# RAM_Board_trex.net
KiCad netlist of a schematic drawn in EAGLE
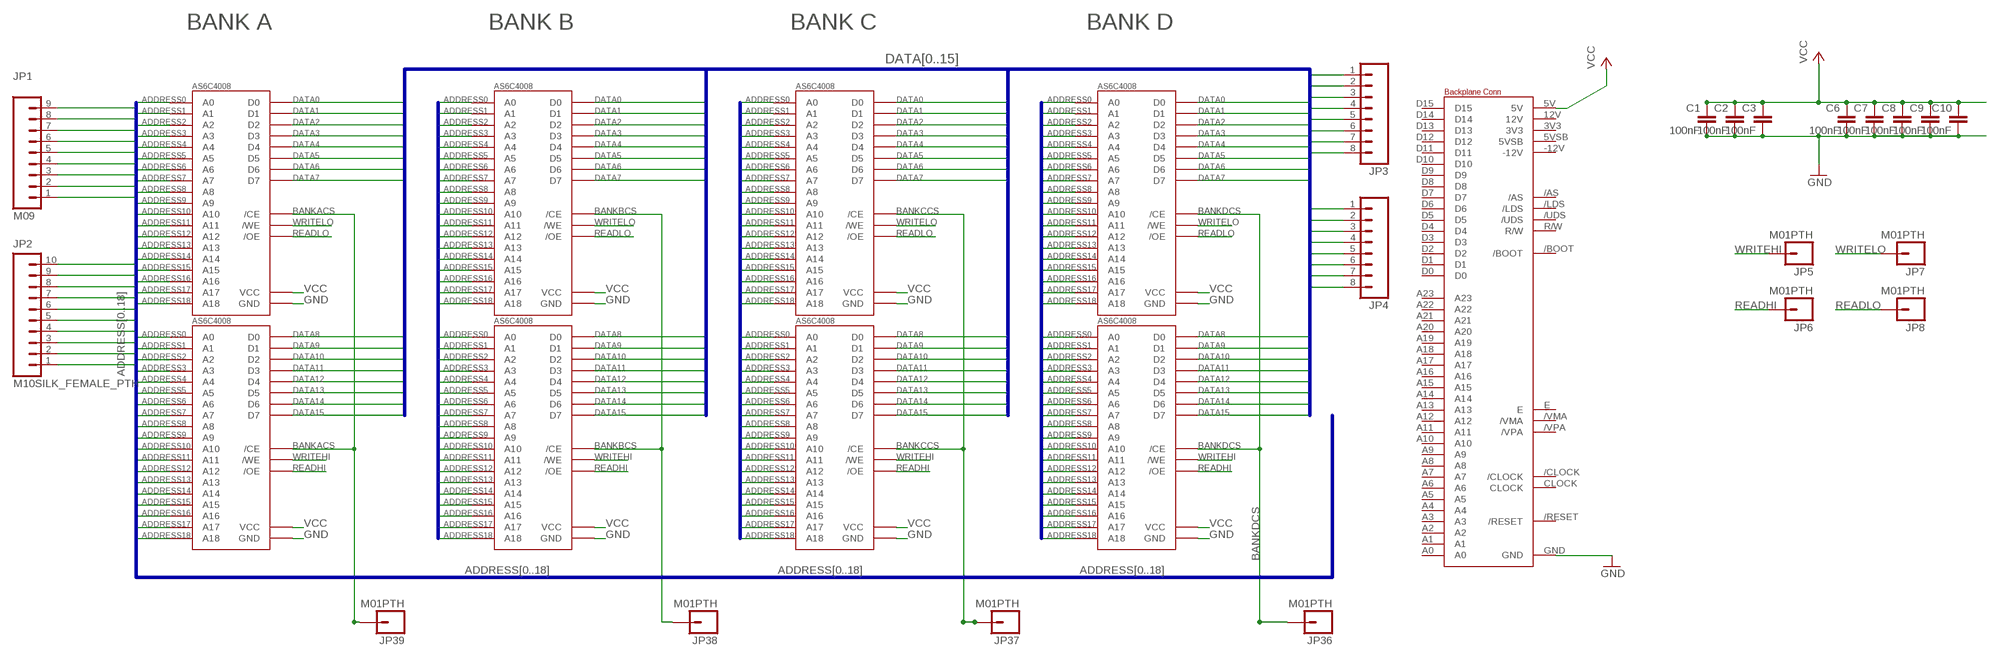
[diagram p0: schematic, sheet 1]

(export (version "E")
  (design (tool "Eeschema 10.0.6"))
  (components
    (comp (ref "AH")
      (value "AS6C4008")
      (footprint "eagle-import:DIL32")
      (libsource (lib "eagle-import") (part "AS6C4008"))
    )
    (comp (ref "AL")
      (value "AS6C4008")
      (footprint "eagle-import:DIL32")
      (libsource (lib "eagle-import") (part "AS6C4008"))
    )
    (comp (ref "BH")
      (value "AS6C4008")
      (footprint "eagle-import:DIL32")
      (libsource (lib "eagle-import") (part "AS6C4008"))
    )
    (comp (ref "BL")
      (value "AS6C4008")
      (footprint "eagle-import:DIL32")
      (libsource (lib "eagle-import") (part "AS6C4008"))
    )
    (comp (ref "C1")
      (value "100nF")
      (footprint "eagle-import:CAP-PTH-SMALL")
      (libsource (lib "eagle-import") (part "CAPPTH"))
    )
    (comp (ref "C2")
      (value "100nF")
      (footprint "eagle-import:CAP-PTH-SMALL")
      (libsource (lib "eagle-import") (part "CAPPTH"))
    )
    (comp (ref "C3")
      (value "100nF")
      (footprint "eagle-import:CAP-PTH-SMALL")
      (libsource (lib "eagle-import") (part "CAPPTH"))
    )
    (comp (ref "C6")
      (value "100nF")
      (footprint "eagle-import:CAP-PTH-SMALL")
      (libsource (lib "eagle-import") (part "CAPPTH"))
    )
    (comp (ref "C7")
      (value "100nF")
      (footprint "eagle-import:CAP-PTH-SMALL")
      (libsource (lib "eagle-import") (part "CAPPTH"))
    )
    (comp (ref "C8")
      (value "100nF")
      (footprint "eagle-import:CAP-PTH-SMALL")
      (libsource (lib "eagle-import") (part "CAPPTH"))
    )
    (comp (ref "C9")
      (value "100nF")
      (footprint "eagle-import:CAP-PTH-SMALL")
      (libsource (lib "eagle-import") (part "CAPPTH"))
    )
    (comp (ref "C10")
      (value "100nF")
      (footprint "eagle-import:CAP-PTH-SMALL")
      (libsource (lib "eagle-import") (part "CAPPTH"))
    )
    (comp (ref "CH")
      (value "AS6C4008")
      (footprint "eagle-import:DIL32")
      (libsource (lib "eagle-import") (part "AS6C4008"))
    )
    (comp (ref "CL")
      (value "AS6C4008")
      (footprint "eagle-import:DIL32")
      (libsource (lib "eagle-import") (part "AS6C4008"))
    )
    (comp (ref "DH")
      (value "AS6C4008")
      (footprint "eagle-import:DIL32")
      (libsource (lib "eagle-import") (part "AS6C4008"))
    )
    (comp (ref "DL")
      (value "AS6C4008")
      (footprint "eagle-import:DIL32")
      (libsource (lib "eagle-import") (part "AS6C4008"))
    )
    (comp (ref "JP1")
      (value "M09")
      (footprint "eagle-import:1X09")
      (libsource (lib "eagle-import") (part "M09"))
    )
    (comp (ref "JP2")
      (value "M10SILK_FEMALE_PTH")
      (footprint "eagle-import:1X10")
      (libsource (lib "eagle-import") (part "M10SILK_FEMALE_PTH"))
    )
    (comp (ref "JP3")
      (value "M08")
      (footprint "eagle-import:1X08_ROUND")
      (libsource (lib "eagle-import") (part "M08"))
    )
    (comp (ref "JP4")
      (value "M08")
      (footprint "eagle-import:1X08_ROUND")
      (libsource (lib "eagle-import") (part "M08"))
    )
    (comp (ref "JP5")
      (value "M01PTH")
      (footprint "eagle-import:1X01")
      (libsource (lib "eagle-import") (part "M01PTH"))
    )
    (comp (ref "JP6")
      (value "M01PTH")
      (footprint "eagle-import:1X01")
      (libsource (lib "eagle-import") (part "M01PTH"))
    )
    (comp (ref "JP7")
      (value "M01PTH")
      (footprint "eagle-import:1X01")
      (libsource (lib "eagle-import") (part "M01PTH"))
    )
    (comp (ref "JP8")
      (value "M01PTH")
      (footprint "eagle-import:1X01")
      (libsource (lib "eagle-import") (part "M01PTH"))
    )
    (comp (ref "JP36")
      (value "M01PTH")
      (footprint "eagle-import:1X01")
      (libsource (lib "eagle-import") (part "M01PTH"))
    )
    (comp (ref "JP37")
      (value "M01PTH")
      (footprint "eagle-import:1X01")
      (libsource (lib "eagle-import") (part "M01PTH"))
    )
    (comp (ref "JP38")
      (value "M01PTH")
      (footprint "eagle-import:1X01")
      (libsource (lib "eagle-import") (part "M01PTH"))
    )
    (comp (ref "JP39")
      (value "M01PTH")
      (footprint "eagle-import:1X01")
      (libsource (lib "eagle-import") (part "M01PTH"))
    )
    (comp (ref "U$1")
      (value "BACKPLANECONN")
      (footprint "eagle-import:BLANKBOARD")
      (libsource (lib "eagle-import") (part "BACKPLANECONN"))
    )
  )
  (nets
    (net (code "3") (name "ADDRESS0") (class "Default")
      (node (ref "AH") (pin "12") (pinfunction "A0_12") (pintype "input"))
      (node (ref "AL") (pin "12") (pinfunction "A0_12") (pintype "input"))
      (node (ref "BH") (pin "12") (pinfunction "A0_12") (pintype "input"))
      (node (ref "BL") (pin "12") (pinfunction "A0_12") (pintype "input"))
      (node (ref "CH") (pin "12") (pinfunction "A0_12") (pintype "input"))
      (node (ref "CL") (pin "12") (pinfunction "A0_12") (pintype "input"))
      (node (ref "DH") (pin "12") (pinfunction "A0_12") (pintype "input"))
      (node (ref "DL") (pin "12") (pinfunction "A0_12") (pintype "input"))
      (node (ref "JP1") (pin "9") (pinfunction "9_9") (pintype "passive"))
    )
    (net (code "4") (name "ADDRESS1") (class "Default")
      (node (ref "AH") (pin "11") (pinfunction "A1_11") (pintype "input"))
      (node (ref "AL") (pin "11") (pinfunction "A1_11") (pintype "input"))
      (node (ref "BH") (pin "11") (pinfunction "A1_11") (pintype "input"))
      (node (ref "BL") (pin "11") (pinfunction "A1_11") (pintype "input"))
      (node (ref "CH") (pin "11") (pinfunction "A1_11") (pintype "input"))
      (node (ref "CL") (pin "11") (pinfunction "A1_11") (pintype "input"))
      (node (ref "DH") (pin "11") (pinfunction "A1_11") (pintype "input"))
      (node (ref "DL") (pin "11") (pinfunction "A1_11") (pintype "input"))
      (node (ref "JP1") (pin "8") (pinfunction "8_8") (pintype "passive"))
    )
    (net (code "5") (name "ADDRESS2") (class "Default")
      (node (ref "AH") (pin "10") (pinfunction "A2_10") (pintype "input"))
      (node (ref "AL") (pin "10") (pinfunction "A2_10") (pintype "input"))
      (node (ref "BH") (pin "10") (pinfunction "A2_10") (pintype "input"))
      (node (ref "BL") (pin "10") (pinfunction "A2_10") (pintype "input"))
      (node (ref "CH") (pin "10") (pinfunction "A2_10") (pintype "input"))
      (node (ref "CL") (pin "10") (pinfunction "A2_10") (pintype "input"))
      (node (ref "DH") (pin "10") (pinfunction "A2_10") (pintype "input"))
      (node (ref "DL") (pin "10") (pinfunction "A2_10") (pintype "input"))
      (node (ref "JP1") (pin "7") (pinfunction "7_7") (pintype "passive"))
    )
    (net (code "6") (name "ADDRESS3") (class "Default")
      (node (ref "AH") (pin "9") (pinfunction "A3_9") (pintype "input"))
      (node (ref "AL") (pin "9") (pinfunction "A3_9") (pintype "input"))
      (node (ref "BH") (pin "9") (pinfunction "A3_9") (pintype "input"))
      (node (ref "BL") (pin "9") (pinfunction "A3_9") (pintype "input"))
      (node (ref "CH") (pin "9") (pinfunction "A3_9") (pintype "input"))
      (node (ref "CL") (pin "9") (pinfunction "A3_9") (pintype "input"))
      (node (ref "DH") (pin "9") (pinfunction "A3_9") (pintype "input"))
      (node (ref "DL") (pin "9") (pinfunction "A3_9") (pintype "input"))
      (node (ref "JP1") (pin "6") (pinfunction "6_6") (pintype "passive"))
    )
    (net (code "7") (name "ADDRESS4") (class "Default")
      (node (ref "AH") (pin "8") (pinfunction "A4_8") (pintype "input"))
      (node (ref "AL") (pin "8") (pinfunction "A4_8") (pintype "input"))
      (node (ref "BH") (pin "8") (pinfunction "A4_8") (pintype "input"))
      (node (ref "BL") (pin "8") (pinfunction "A4_8") (pintype "input"))
      (node (ref "CH") (pin "8") (pinfunction "A4_8") (pintype "input"))
      (node (ref "CL") (pin "8") (pinfunction "A4_8") (pintype "input"))
      (node (ref "DH") (pin "8") (pinfunction "A4_8") (pintype "input"))
      (node (ref "DL") (pin "8") (pinfunction "A4_8") (pintype "input"))
      (node (ref "JP1") (pin "5") (pinfunction "5_5") (pintype "passive"))
    )
    (net (code "8") (name "ADDRESS5") (class "Default")
      (node (ref "AH") (pin "7") (pinfunction "A5_7") (pintype "input"))
      (node (ref "AL") (pin "7") (pinfunction "A5_7") (pintype "input"))
      (node (ref "BH") (pin "7") (pinfunction "A5_7") (pintype "input"))
      (node (ref "BL") (pin "7") (pinfunction "A5_7") (pintype "input"))
      (node (ref "CH") (pin "7") (pinfunction "A5_7") (pintype "input"))
      (node (ref "CL") (pin "7") (pinfunction "A5_7") (pintype "input"))
      (node (ref "DH") (pin "7") (pinfunction "A5_7") (pintype "input"))
      (node (ref "DL") (pin "7") (pinfunction "A5_7") (pintype "input"))
      (node (ref "JP1") (pin "4") (pinfunction "4_4") (pintype "passive"))
    )
    (net (code "9") (name "ADDRESS6") (class "Default")
      (node (ref "AH") (pin "6") (pinfunction "A6_6") (pintype "input"))
      (node (ref "AL") (pin "6") (pinfunction "A6_6") (pintype "input"))
      (node (ref "BH") (pin "6") (pinfunction "A6_6") (pintype "input"))
      (node (ref "BL") (pin "6") (pinfunction "A6_6") (pintype "input"))
      (node (ref "CH") (pin "6") (pinfunction "A6_6") (pintype "input"))
      (node (ref "CL") (pin "6") (pinfunction "A6_6") (pintype "input"))
      (node (ref "DH") (pin "6") (pinfunction "A6_6") (pintype "input"))
      (node (ref "DL") (pin "6") (pinfunction "A6_6") (pintype "input"))
      (node (ref "JP1") (pin "3") (pinfunction "3_3") (pintype "passive"))
    )
    (net (code "10") (name "ADDRESS7") (class "Default")
      (node (ref "AH") (pin "5") (pinfunction "A7_5") (pintype "input"))
      (node (ref "AL") (pin "5") (pinfunction "A7_5") (pintype "input"))
      (node (ref "BH") (pin "5") (pinfunction "A7_5") (pintype "input"))
      (node (ref "BL") (pin "5") (pinfunction "A7_5") (pintype "input"))
      (node (ref "CH") (pin "5") (pinfunction "A7_5") (pintype "input"))
      (node (ref "CL") (pin "5") (pinfunction "A7_5") (pintype "input"))
      (node (ref "DH") (pin "5") (pinfunction "A7_5") (pintype "input"))
      (node (ref "DL") (pin "5") (pinfunction "A7_5") (pintype "input"))
      (node (ref "JP1") (pin "2") (pinfunction "2_2") (pintype "passive"))
    )
    (net (code "11") (name "ADDRESS8") (class "Default")
      (node (ref "AH") (pin "27") (pinfunction "A8_27") (pintype "input"))
      (node (ref "AL") (pin "27") (pinfunction "A8_27") (pintype "input"))
      (node (ref "BH") (pin "27") (pinfunction "A8_27") (pintype "input"))
      (node (ref "BL") (pin "27") (pinfunction "A8_27") (pintype "input"))
      (node (ref "CH") (pin "27") (pinfunction "A8_27") (pintype "input"))
      (node (ref "CL") (pin "27") (pinfunction "A8_27") (pintype "input"))
      (node (ref "DH") (pin "27") (pinfunction "A8_27") (pintype "input"))
      (node (ref "DL") (pin "27") (pinfunction "A8_27") (pintype "input"))
      (node (ref "JP1") (pin "1") (pinfunction "1_1") (pintype "passive"))
    )
    (net (code "12") (name "ADDRESS9") (class "Default")
      (node (ref "AH") (pin "26") (pinfunction "A9_26") (pintype "input"))
      (node (ref "AL") (pin "26") (pinfunction "A9_26") (pintype "input"))
      (node (ref "BH") (pin "26") (pinfunction "A9_26") (pintype "input"))
      (node (ref "BL") (pin "26") (pinfunction "A9_26") (pintype "input"))
      (node (ref "CH") (pin "26") (pinfunction "A9_26") (pintype "input"))
      (node (ref "CL") (pin "26") (pinfunction "A9_26") (pintype "input"))
      (node (ref "DH") (pin "26") (pinfunction "A9_26") (pintype "input"))
      (node (ref "DL") (pin "26") (pinfunction "A9_26") (pintype "input"))
      (node (ref "JP2") (pin "10") (pinfunction "10_10") (pintype "passive"))
    )
    (net (code "13") (name "ADDRESS10") (class "Default")
      (node (ref "AH") (pin "23") (pinfunction "A10_23") (pintype "input"))
      (node (ref "AL") (pin "23") (pinfunction "A10_23") (pintype "input"))
      (node (ref "BH") (pin "23") (pinfunction "A10_23") (pintype "input"))
      (node (ref "BL") (pin "23") (pinfunction "A10_23") (pintype "input"))
      (node (ref "CH") (pin "23") (pinfunction "A10_23") (pintype "input"))
      (node (ref "CL") (pin "23") (pinfunction "A10_23") (pintype "input"))
      (node (ref "DH") (pin "23") (pinfunction "A10_23") (pintype "input"))
      (node (ref "DL") (pin "23") (pinfunction "A10_23") (pintype "input"))
      (node (ref "JP2") (pin "9") (pinfunction "9_9") (pintype "passive"))
    )
    (net (code "14") (name "ADDRESS11") (class "Default")
      (node (ref "AH") (pin "25") (pinfunction "A11_25") (pintype "input"))
      (node (ref "AL") (pin "25") (pinfunction "A11_25") (pintype "input"))
      (node (ref "BH") (pin "25") (pinfunction "A11_25") (pintype "input"))
      (node (ref "BL") (pin "25") (pinfunction "A11_25") (pintype "input"))
      (node (ref "CH") (pin "25") (pinfunction "A11_25") (pintype "input"))
      (node (ref "CL") (pin "25") (pinfunction "A11_25") (pintype "input"))
      (node (ref "DH") (pin "25") (pinfunction "A11_25") (pintype "input"))
      (node (ref "DL") (pin "25") (pinfunction "A11_25") (pintype "input"))
      (node (ref "JP2") (pin "8") (pinfunction "8_8") (pintype "passive"))
    )
    (net (code "15") (name "ADDRESS12") (class "Default")
      (node (ref "AH") (pin "4") (pinfunction "A12_4") (pintype "input"))
      (node (ref "AL") (pin "4") (pinfunction "A12_4") (pintype "input"))
      (node (ref "BH") (pin "4") (pinfunction "A12_4") (pintype "input"))
      (node (ref "BL") (pin "4") (pinfunction "A12_4") (pintype "input"))
      (node (ref "CH") (pin "4") (pinfunction "A12_4") (pintype "input"))
      (node (ref "CL") (pin "4") (pinfunction "A12_4") (pintype "input"))
      (node (ref "DH") (pin "4") (pinfunction "A12_4") (pintype "input"))
      (node (ref "DL") (pin "4") (pinfunction "A12_4") (pintype "input"))
      (node (ref "JP2") (pin "7") (pinfunction "7_7") (pintype "passive"))
    )
    (net (code "16") (name "ADDRESS13") (class "Default")
      (node (ref "AH") (pin "28") (pinfunction "A13_28") (pintype "input"))
      (node (ref "AL") (pin "28") (pinfunction "A13_28") (pintype "input"))
      (node (ref "BH") (pin "28") (pinfunction "A13_28") (pintype "input"))
      (node (ref "BL") (pin "28") (pinfunction "A13_28") (pintype "input"))
      (node (ref "CH") (pin "28") (pinfunction "A13_28") (pintype "input"))
      (node (ref "CL") (pin "28") (pinfunction "A13_28") (pintype "input"))
      (node (ref "DH") (pin "28") (pinfunction "A13_28") (pintype "input"))
      (node (ref "DL") (pin "28") (pinfunction "A13_28") (pintype "input"))
      (node (ref "JP2") (pin "6") (pinfunction "6_6") (pintype "passive"))
    )
    (net (code "17") (name "ADDRESS14") (class "Default")
      (node (ref "AH") (pin "3") (pinfunction "A14_3") (pintype "input"))
      (node (ref "AL") (pin "3") (pinfunction "A14_3") (pintype "input"))
      (node (ref "BH") (pin "3") (pinfunction "A14_3") (pintype "input"))
      (node (ref "BL") (pin "3") (pinfunction "A14_3") (pintype "input"))
      (node (ref "CH") (pin "3") (pinfunction "A14_3") (pintype "input"))
      (node (ref "CL") (pin "3") (pinfunction "A14_3") (pintype "input"))
      (node (ref "DH") (pin "3") (pinfunction "A14_3") (pintype "input"))
      (node (ref "DL") (pin "3") (pinfunction "A14_3") (pintype "input"))
      (node (ref "JP2") (pin "5") (pinfunction "5_5") (pintype "passive"))
    )
    (net (code "18") (name "ADDRESS15") (class "Default")
      (node (ref "AH") (pin "31") (pinfunction "A15_31") (pintype "input"))
      (node (ref "AL") (pin "31") (pinfunction "A15_31") (pintype "input"))
      (node (ref "BH") (pin "31") (pinfunction "A15_31") (pintype "input"))
      (node (ref "BL") (pin "31") (pinfunction "A15_31") (pintype "input"))
      (node (ref "CH") (pin "31") (pinfunction "A15_31") (pintype "input"))
      (node (ref "CL") (pin "31") (pinfunction "A15_31") (pintype "input"))
      (node (ref "DH") (pin "31") (pinfunction "A15_31") (pintype "input"))
      (node (ref "DL") (pin "31") (pinfunction "A15_31") (pintype "input"))
      (node (ref "JP2") (pin "4") (pinfunction "4_4") (pintype "passive"))
    )
    (net (code "19") (name "ADDRESS16") (class "Default")
      (node (ref "AH") (pin "2") (pinfunction "A16_2") (pintype "input"))
      (node (ref "AL") (pin "2") (pinfunction "A16_2") (pintype "input"))
      (node (ref "BH") (pin "2") (pinfunction "A16_2") (pintype "input"))
      (node (ref "BL") (pin "2") (pinfunction "A16_2") (pintype "input"))
      (node (ref "CH") (pin "2") (pinfunction "A16_2") (pintype "input"))
      (node (ref "CL") (pin "2") (pinfunction "A16_2") (pintype "input"))
      (node (ref "DH") (pin "2") (pinfunction "A16_2") (pintype "input"))
      (node (ref "DL") (pin "2") (pinfunction "A16_2") (pintype "input"))
      (node (ref "JP2") (pin "3") (pinfunction "3_3") (pintype "passive"))
    )
    (net (code "20") (name "ADDRESS17") (class "Default")
      (node (ref "AH") (pin "30") (pinfunction "A17_30") (pintype "input"))
      (node (ref "AL") (pin "30") (pinfunction "A17_30") (pintype "input"))
      (node (ref "BH") (pin "30") (pinfunction "A17_30") (pintype "input"))
      (node (ref "BL") (pin "30") (pinfunction "A17_30") (pintype "input"))
      (node (ref "CH") (pin "30") (pinfunction "A17_30") (pintype "input"))
      (node (ref "CL") (pin "30") (pinfunction "A17_30") (pintype "input"))
      (node (ref "DH") (pin "30") (pinfunction "A17_30") (pintype "input"))
      (node (ref "DL") (pin "30") (pinfunction "A17_30") (pintype "input"))
      (node (ref "JP2") (pin "2") (pinfunction "2_2") (pintype "passive"))
    )
    (net (code "21") (name "ADDRESS18") (class "Default")
      (node (ref "AH") (pin "1") (pinfunction "A18_1") (pintype "input"))
      (node (ref "AL") (pin "1") (pinfunction "A18_1") (pintype "input"))
      (node (ref "BH") (pin "1") (pinfunction "A18_1") (pintype "input"))
      (node (ref "BL") (pin "1") (pinfunction "A18_1") (pintype "input"))
      (node (ref "CH") (pin "1") (pinfunction "A18_1") (pintype "input"))
      (node (ref "CL") (pin "1") (pinfunction "A18_1") (pintype "input"))
      (node (ref "DH") (pin "1") (pinfunction "A18_1") (pintype "input"))
      (node (ref "DL") (pin "1") (pinfunction "A18_1") (pintype "input"))
      (node (ref "JP2") (pin "1") (pinfunction "1_1") (pintype "passive"))
    )
    (net (code "22") (name "BANKACS") (class "Default")
      (node (ref "AH") (pin "22") (pinfunction "/CE_22") (pintype "input"))
      (node (ref "AL") (pin "22") (pinfunction "/CE_22") (pintype "input"))
      (node (ref "JP39") (pin "1") (pinfunction "1_1") (pintype "passive"))
    )
    (net (code "23") (name "BANKBCS") (class "Default")
      (node (ref "BH") (pin "22") (pinfunction "/CE_22") (pintype "input"))
      (node (ref "BL") (pin "22") (pinfunction "/CE_22") (pintype "input"))
      (node (ref "JP38") (pin "1") (pinfunction "1_1") (pintype "passive"))
    )
    (net (code "24") (name "BANKCCS") (class "Default")
      (node (ref "CH") (pin "22") (pinfunction "/CE_22") (pintype "input"))
      (node (ref "CL") (pin "22") (pinfunction "/CE_22") (pintype "input"))
      (node (ref "JP37") (pin "1") (pinfunction "1_1") (pintype "passive"))
    )
    (net (code "25") (name "BANKDCS") (class "Default")
      (node (ref "DH") (pin "22") (pinfunction "/CE_22") (pintype "input"))
      (node (ref "DL") (pin "22") (pinfunction "/CE_22") (pintype "input"))
      (node (ref "JP36") (pin "1") (pinfunction "1_1") (pintype "passive"))
    )
    (net (code "26") (name "DATA0") (class "Default")
      (node (ref "AL") (pin "13") (pinfunction "D0_13") (pintype "input"))
      (node (ref "BL") (pin "13") (pinfunction "D0_13") (pintype "input"))
      (node (ref "CL") (pin "13") (pinfunction "D0_13") (pintype "input"))
      (node (ref "DL") (pin "13") (pinfunction "D0_13") (pintype "input"))
      (node (ref "JP3") (pin "1") (pinfunction "1_1") (pintype "passive"))
    )
    (net (code "27") (name "DATA1") (class "Default")
      (node (ref "AL") (pin "14") (pinfunction "D1_14") (pintype "input"))
      (node (ref "BL") (pin "14") (pinfunction "D1_14") (pintype "input"))
      (node (ref "CL") (pin "14") (pinfunction "D1_14") (pintype "input"))
      (node (ref "DL") (pin "14") (pinfunction "D1_14") (pintype "input"))
      (node (ref "JP3") (pin "2") (pinfunction "2_2") (pintype "passive"))
    )
    (net (code "28") (name "DATA2") (class "Default")
      (node (ref "AL") (pin "15") (pinfunction "D2_15") (pintype "input"))
      (node (ref "BL") (pin "15") (pinfunction "D2_15") (pintype "input"))
      (node (ref "CL") (pin "15") (pinfunction "D2_15") (pintype "input"))
      (node (ref "DL") (pin "15") (pinfunction "D2_15") (pintype "input"))
      (node (ref "JP3") (pin "3") (pinfunction "3_3") (pintype "passive"))
    )
    (net (code "29") (name "DATA3") (class "Default")
      (node (ref "AL") (pin "17") (pinfunction "D3_17") (pintype "input"))
      (node (ref "BL") (pin "17") (pinfunction "D3_17") (pintype "input"))
      (node (ref "CL") (pin "17") (pinfunction "D3_17") (pintype "input"))
      (node (ref "DL") (pin "17") (pinfunction "D3_17") (pintype "input"))
      (node (ref "JP3") (pin "4") (pinfunction "4_4") (pintype "passive"))
    )
    (net (code "30") (name "DATA4") (class "Default")
      (node (ref "AL") (pin "18") (pinfunction "D4_18") (pintype "input"))
      (node (ref "BL") (pin "18") (pinfunction "D4_18") (pintype "input"))
      (node (ref "CL") (pin "18") (pinfunction "D4_18") (pintype "input"))
      (node (ref "DL") (pin "18") (pinfunction "D4_18") (pintype "input"))
      (node (ref "JP3") (pin "5") (pinfunction "5_5") (pintype "passive"))
    )
    (net (code "31") (name "DATA5") (class "Default")
      (node (ref "AL") (pin "19") (pinfunction "D5_19") (pintype "input"))
      (node (ref "BL") (pin "19") (pinfunction "D5_19") (pintype "input"))
      (node (ref "CL") (pin "19") (pinfunction "D5_19") (pintype "input"))
      (node (ref "DL") (pin "19") (pinfunction "D5_19") (pintype "input"))
      (node (ref "JP3") (pin "6") (pinfunction "6_6") (pintype "passive"))
    )
    (net (code "32") (name "DATA6") (class "Default")
      (node (ref "AL") (pin "20") (pinfunction "D6_20") (pintype "input"))
      (node (ref "BL") (pin "20") (pinfunction "D6_20") (pintype "input"))
      (node (ref "CL") (pin "20") (pinfunction "D6_20") (pintype "input"))
      (node (ref "DL") (pin "20") (pinfunction "D6_20") (pintype "input"))
      (node (ref "JP3") (pin "7") (pinfunction "7_7") (pintype "passive"))
    )
    (net (code "33") (name "DATA7") (class "Default")
      (node (ref "AL") (pin "21") (pinfunction "D7_21") (pintype "input"))
      (node (ref "BL") (pin "21") (pinfunction "D7_21") (pintype "input"))
      (node (ref "CL") (pin "21") (pinfunction "D7_21") (pintype "input"))
      (node (ref "DL") (pin "21") (pinfunction "D7_21") (pintype "input"))
      (node (ref "JP3") (pin "8") (pinfunction "8_8") (pintype "passive"))
    )
    (net (code "34") (name "DATA8") (class "Default")
      (node (ref "AH") (pin "13") (pinfunction "D0_13") (pintype "input"))
      (node (ref "BH") (pin "13") (pinfunction "D0_13") (pintype "input"))
      (node (ref "CH") (pin "13") (pinfunction "D0_13") (pintype "input"))
      (node (ref "DH") (pin "13") (pinfunction "D0_13") (pintype "input"))
      (node (ref "JP4") (pin "1") (pinfunction "1_1") (pintype "passive"))
    )
    (net (code "35") (name "DATA9") (class "Default")
      (node (ref "AH") (pin "14") (pinfunction "D1_14") (pintype "input"))
      (node (ref "BH") (pin "14") (pinfunction "D1_14") (pintype "input"))
      (node (ref "CH") (pin "14") (pinfunction "D1_14") (pintype "input"))
      (node (ref "DH") (pin "14") (pinfunction "D1_14") (pintype "input"))
      (node (ref "JP4") (pin "2") (pinfunction "2_2") (pintype "passive"))
    )
    (net (code "36") (name "DATA10") (class "Default")
      (node (ref "AH") (pin "15") (pinfunction "D2_15") (pintype "input"))
      (node (ref "BH") (pin "15") (pinfunction "D2_15") (pintype "input"))
      (node (ref "CH") (pin "15") (pinfunction "D2_15") (pintype "input"))
      (node (ref "DH") (pin "15") (pinfunction "D2_15") (pintype "input"))
      (node (ref "JP4") (pin "3") (pinfunction "3_3") (pintype "passive"))
    )
    (net (code "37") (name "DATA11") (class "Default")
      (node (ref "AH") (pin "17") (pinfunction "D3_17") (pintype "input"))
      (node (ref "BH") (pin "17") (pinfunction "D3_17") (pintype "input"))
      (node (ref "CH") (pin "17") (pinfunction "D3_17") (pintype "input"))
      (node (ref "DH") (pin "17") (pinfunction "D3_17") (pintype "input"))
      (node (ref "JP4") (pin "4") (pinfunction "4_4") (pintype "passive"))
    )
    (net (code "38") (name "DATA12") (class "Default")
      (node (ref "AH") (pin "18") (pinfunction "D4_18") (pintype "input"))
      (node (ref "BH") (pin "18") (pinfunction "D4_18") (pintype "input"))
      (node (ref "CH") (pin "18") (pinfunction "D4_18") (pintype "input"))
      (node (ref "DH") (pin "18") (pinfunction "D4_18") (pintype "input"))
      (node (ref "JP4") (pin "5") (pinfunction "5_5") (pintype "passive"))
    )
    (net (code "39") (name "DATA13") (class "Default")
      (node (ref "AH") (pin "19") (pinfunction "D5_19") (pintype "input"))
      (node (ref "BH") (pin "19") (pinfunction "D5_19") (pintype "input"))
      (node (ref "CH") (pin "19") (pinfunction "D5_19") (pintype "input"))
      (node (ref "DH") (pin "19") (pinfunction "D5_19") (pintype "input"))
      (node (ref "JP4") (pin "6") (pinfunction "6_6") (pintype "passive"))
    )
    (net (code "40") (name "DATA14") (class "Default")
      (node (ref "AH") (pin "20") (pinfunction "D6_20") (pintype "input"))
      (node (ref "BH") (pin "20") (pinfunction "D6_20") (pintype "input"))
      (node (ref "CH") (pin "20") (pinfunction "D6_20") (pintype "input"))
      (node (ref "DH") (pin "20") (pinfunction "D6_20") (pintype "input"))
      (node (ref "JP4") (pin "7") (pinfunction "7_7") (pintype "passive"))
    )
    (net (code "41") (name "DATA15") (class "Default")
      (node (ref "AH") (pin "21") (pinfunction "D7_21") (pintype "input"))
      (node (ref "BH") (pin "21") (pinfunction "D7_21") (pintype "input"))
      (node (ref "CH") (pin "21") (pinfunction "D7_21") (pintype "input"))
      (node (ref "DH") (pin "21") (pinfunction "D7_21") (pintype "input"))
      (node (ref "JP4") (pin "8") (pinfunction "8_8") (pintype "passive"))
    )
    (net (code "42") (name "GND") (class "Default")
      (node (ref "AH") (pin "16") (pinfunction "GND_16") (pintype "input"))
      (node (ref "AL") (pin "16") (pinfunction "GND_16") (pintype "input"))
      (node (ref "BH") (pin "16") (pinfunction "GND_16") (pintype "input"))
      (node (ref "BL") (pin "16") (pinfunction "GND_16") (pintype "input"))
      (node (ref "C1") (pin "2") (pinfunction "2_2") (pintype "passive"))
      (node (ref "C10") (pin "2") (pinfunction "2_2") (pintype "passive"))
      (node (ref "C2") (pin "2") (pinfunction "2_2") (pintype "passive"))
      (node (ref "C3") (pin "2") (pinfunction "2_2") (pintype "passive"))
      (node (ref "C6") (pin "2") (pinfunction "2_2") (pintype "passive"))
      (node (ref "C7") (pin "2") (pinfunction "2_2") (pintype "passive"))
      (node (ref "C8") (pin "2") (pinfunction "2_2") (pintype "passive"))
      (node (ref "C9") (pin "2") (pinfunction "2_2") (pintype "passive"))
      (node (ref "CH") (pin "16") (pinfunction "GND_16") (pintype "input"))
      (node (ref "CL") (pin "16") (pinfunction "GND_16") (pintype "input"))
      (node (ref "DH") (pin "16") (pinfunction "GND_16") (pintype "input"))
      (node (ref "DL") (pin "16") (pinfunction "GND_16") (pintype "input"))
      (node (ref "U$1") (pin "GND") (pinfunction "GND_GND") (pintype "bidirectional"))
    )
    (net (code "43") (name "READHI") (class "Default")
      (node (ref "AH") (pin "24") (pinfunction "/OE_24") (pintype "input"))
      (node (ref "BH") (pin "24") (pinfunction "/OE_24") (pintype "input"))
      (node (ref "CH") (pin "24") (pinfunction "/OE_24") (pintype "input"))
      (node (ref "DH") (pin "24") (pinfunction "/OE_24") (pintype "input"))
      (node (ref "JP6") (pin "1") (pinfunction "1_1") (pintype "passive"))
    )
    (net (code "44") (name "READLO") (class "Default")
      (node (ref "AL") (pin "24") (pinfunction "/OE_24") (pintype "input"))
      (node (ref "BL") (pin "24") (pinfunction "/OE_24") (pintype "input"))
      (node (ref "CL") (pin "24") (pinfunction "/OE_24") (pintype "input"))
      (node (ref "DL") (pin "24") (pinfunction "/OE_24") (pintype "input"))
      (node (ref "JP8") (pin "1") (pinfunction "1_1") (pintype "passive"))
    )
    (net (code "45") (name "VCC") (class "Default")
      (node (ref "AH") (pin "32") (pinfunction "VCC_32") (pintype "input"))
      (node (ref "AL") (pin "32") (pinfunction "VCC_32") (pintype "input"))
      (node (ref "BH") (pin "32") (pinfunction "VCC_32") (pintype "input"))
      (node (ref "BL") (pin "32") (pinfunction "VCC_32") (pintype "input"))
      (node (ref "C1") (pin "1") (pinfunction "1_1") (pintype "passive"))
      (node (ref "C10") (pin "1") (pinfunction "1_1") (pintype "passive"))
      (node (ref "C2") (pin "1") (pinfunction "1_1") (pintype "passive"))
      (node (ref "C3") (pin "1") (pinfunction "1_1") (pintype "passive"))
      (node (ref "C6") (pin "1") (pinfunction "1_1") (pintype "passive"))
      (node (ref "C7") (pin "1") (pinfunction "1_1") (pintype "passive"))
      (node (ref "C8") (pin "1") (pinfunction "1_1") (pintype "passive"))
      (node (ref "C9") (pin "1") (pinfunction "1_1") (pintype "passive"))
      (node (ref "CH") (pin "32") (pinfunction "VCC_32") (pintype "input"))
      (node (ref "CL") (pin "32") (pinfunction "VCC_32") (pintype "input"))
      (node (ref "DH") (pin "32") (pinfunction "VCC_32") (pintype "input"))
      (node (ref "DL") (pin "32") (pinfunction "VCC_32") (pintype "input"))
      (node (ref "U$1") (pin "5V") (pinfunction "5V_5V") (pintype "bidirectional"))
    )
    (net (code "46") (name "WRITEHI") (class "Default")
      (node (ref "AH") (pin "29") (pinfunction "/WE_29") (pintype "input"))
      (node (ref "BH") (pin "29") (pinfunction "/WE_29") (pintype "input"))
      (node (ref "CH") (pin "29") (pinfunction "/WE_29") (pintype "input"))
      (node (ref "DH") (pin "29") (pinfunction "/WE_29") (pintype "input"))
      (node (ref "JP5") (pin "1") (pinfunction "1_1") (pintype "passive"))
    )
    (net (code "47") (name "WRITELO") (class "Default")
      (node (ref "AL") (pin "29") (pinfunction "/WE_29") (pintype "input"))
      (node (ref "BL") (pin "29") (pinfunction "/WE_29") (pintype "input"))
      (node (ref "CL") (pin "29") (pinfunction "/WE_29") (pintype "input"))
      (node (ref "DL") (pin "29") (pinfunction "/WE_29") (pintype "input"))
      (node (ref "JP7") (pin "1") (pinfunction "1_1") (pintype "passive"))
    )
    (net (code "48") (name "unconnected-(U$1-Pad-12V)") (class "Default")
      (node (ref "U$1") (pin "-12V") (pinfunction "-12V_-12V") (pintype "bidirectional"))
    )
    (net (code "49") (name "unconnected-(U$1-Pad3V3)") (class "Default")
      (node (ref "U$1") (pin "3V3") (pinfunction "3V3_3V3") (pintype "bidirectional"))
    )
    (net (code "50") (name "unconnected-(U$1-Pad5VSB)") (class "Default")
      (node (ref "U$1") (pin "5VSB") (pinfunction "5VSB_5VSB") (pintype "bidirectional"))
    )
    (net (code "51") (name "unconnected-(U$1-Pad12V)") (class "Default")
      (node (ref "U$1") (pin "12V") (pinfunction "12V_12V") (pintype "bidirectional"))
    )
    (net (code "52") (name "unconnected-(U$1-PadA0)") (class "Default")
      (node (ref "U$1") (pin "A0") (pinfunction "A0_A0") (pintype "bidirectional"))
    )
    (net (code "53") (name "unconnected-(U$1-PadA1)") (class "Default")
      (node (ref "U$1") (pin "A1") (pinfunction "A1_A1") (pintype "bidirectional"))
    )
    (net (code "54") (name "unconnected-(U$1-PadA2)") (class "Default")
      (node (ref "U$1") (pin "A2") (pinfunction "A2_A2") (pintype "bidirectional"))
    )
    (net (code "55") (name "unconnected-(U$1-PadA3)") (class "Default")
      (node (ref "U$1") (pin "A3") (pinfunction "A3_A3") (pintype "bidirectional"))
    )
    (net (code "56") (name "unconnected-(U$1-PadA4)") (class "Default")
      (node (ref "U$1") (pin "A4") (pinfunction "A4_A4") (pintype "bidirectional"))
    )
    (net (code "57") (name "unconnected-(U$1-PadA5)") (class "Default")
      (node (ref "U$1") (pin "A5") (pinfunction "A5_A5") (pintype "bidirectional"))
    )
    (net (code "58") (name "unconnected-(U$1-PadA6)") (class "Default")
      (node (ref "U$1") (pin "A6") (pinfunction "A6_A6") (pintype "bidirectional"))
    )
    (net (code "59") (name "unconnected-(U$1-PadA7)") (class "Default")
      (node (ref "U$1") (pin "A7") (pinfunction "A7_A7") (pintype "bidirectional"))
    )
    (net (code "60") (name "unconnected-(U$1-PadA8)") (class "Default")
      (node (ref "U$1") (pin "A8") (pinfunction "A8_A8") (pintype "bidirectional"))
    )
    (net (code "61") (name "unconnected-(U$1-PadA9)") (class "Default")
      (node (ref "U$1") (pin "A9") (pinfunction "A9_A9") (pintype "bidirectional"))
    )
    (net (code "62") (name "unconnected-(U$1-PadA10)") (class "Default")
      (node (ref "U$1") (pin "A10") (pinfunction "A10_A10") (pintype "bidirectional"))
    )
    (net (code "63") (name "unconnected-(U$1-PadA11)") (class "Default")
      (node (ref "U$1") (pin "A11") (pinfunction "A11_A11") (pintype "bidirectional"))
    )
    (net (code "64") (name "unconnected-(U$1-PadA12)") (class "Default")
      (node (ref "U$1") (pin "A12") (pinfunction "A12_A12") (pintype "bidirectional"))
    )
    (net (code "65") (name "unconnected-(U$1-PadA13)") (class "Default")
      (node (ref "U$1") (pin "A13") (pinfunction "A13_A13") (pintype "bidirectional"))
    )
    (net (code "66") (name "unconnected-(U$1-PadA14)") (class "Default")
      (node (ref "U$1") (pin "A14") (pinfunction "A14_A14") (pintype "bidirectional"))
    )
    (net (code "67") (name "unconnected-(U$1-PadA15)") (class "Default")
      (node (ref "U$1") (pin "A15") (pinfunction "A15_A15") (pintype "bidirectional"))
    )
    (net (code "68") (name "unconnected-(U$1-PadA16)") (class "Default")
      (node (ref "U$1") (pin "A16") (pinfunction "A16_A16") (pintype "bidirectional"))
    )
    (net (code "69") (name "unconnected-(U$1-PadA17)") (class "Default")
      (node (ref "U$1") (pin "A17") (pinfunction "A17_A17") (pintype "bidirectional"))
    )
    (net (code "70") (name "unconnected-(U$1-PadA18)") (class "Default")
      (node (ref "U$1") (pin "A18") (pinfunction "A18_A18") (pintype "bidirectional"))
    )
    (net (code "71") (name "unconnected-(U$1-PadA19)") (class "Default")
      (node (ref "U$1") (pin "A19") (pinfunction "A19_A19") (pintype "bidirectional"))
    )
    (net (code "72") (name "unconnected-(U$1-PadA20)") (class "Default")
      (node (ref "U$1") (pin "A20") (pinfunction "A20_A20") (pintype "bidirectional"))
    )
    (net (code "73") (name "unconnected-(U$1-PadA21)") (class "Default")
      (node (ref "U$1") (pin "A21") (pinfunction "A21_A21") (pintype "bidirectional"))
    )
    (net (code "74") (name "unconnected-(U$1-PadA22)") (class "Default")
      (node (ref "U$1") (pin "A22") (pinfunction "A22_A22") (pintype "bidirectional"))
    )
    (net (code "75") (name "unconnected-(U$1-PadA23)") (class "Default")
      (node (ref "U$1") (pin "A23") (pinfunction "A23_A23") (pintype "bidirectional"))
    )
    (net (code "76") (name "unconnected-(U$1-PadCLOCK)") (class "Default")
      (node (ref "U$1") (pin "CLOCK") (pinfunction "CLOCK_CLOCK") (pintype "bidirectional"))
    )
    (net (code "77") (name "unconnected-(U$1-PadD0)") (class "Default")
      (node (ref "U$1") (pin "D0") (pinfunction "D0_D0") (pintype "bidirectional"))
    )
    (net (code "78") (name "unconnected-(U$1-PadD1)") (class "Default")
      (node (ref "U$1") (pin "D1") (pinfunction "D1_D1") (pintype "bidirectional"))
    )
    (net (code "79") (name "unconnected-(U$1-PadD2)") (class "Default")
      (node (ref "U$1") (pin "D2") (pinfunction "D2_D2") (pintype "bidirectional"))
    )
    (net (code "80") (name "unconnected-(U$1-PadD3)") (class "Default")
      (node (ref "U$1") (pin "D3") (pinfunction "D3_D3") (pintype "bidirectional"))
    )
    (net (code "81") (name "unconnected-(U$1-PadD4)") (class "Default")
      (node (ref "U$1") (pin "D4") (pinfunction "D4_D4") (pintype "bidirectional"))
    )
    (net (code "82") (name "unconnected-(U$1-PadD5)") (class "Default")
      (node (ref "U$1") (pin "D5") (pinfunction "D5_D5") (pintype "bidirectional"))
    )
    (net (code "83") (name "unconnected-(U$1-PadD6)") (class "Default")
      (node (ref "U$1") (pin "D6") (pinfunction "D6_D6") (pintype "bidirectional"))
    )
    (net (code "84") (name "unconnected-(U$1-PadD7)") (class "Default")
      (node (ref "U$1") (pin "D7") (pinfunction "D7_D7") (pintype "bidirectional"))
    )
    (net (code "85") (name "unconnected-(U$1-PadD8)") (class "Default")
      (node (ref "U$1") (pin "D8") (pinfunction "D8_D8") (pintype "bidirectional"))
    )
    (net (code "86") (name "unconnected-(U$1-PadD9)") (class "Default")
      (node (ref "U$1") (pin "D9") (pinfunction "D9_D9") (pintype "bidirectional"))
    )
    (net (code "87") (name "unconnected-(U$1-PadD10)") (class "Default")
      (node (ref "U$1") (pin "D10") (pinfunction "D10_D10") (pintype "bidirectional"))
    )
    (net (code "88") (name "unconnected-(U$1-PadD11)") (class "Default")
      (node (ref "U$1") (pin "D11") (pinfunction "D11_D11") (pintype "bidirectional"))
    )
    (net (code "89") (name "unconnected-(U$1-PadD12)") (class "Default")
      (node (ref "U$1") (pin "D12") (pinfunction "D12_D12") (pintype "bidirectional"))
    )
    (net (code "90") (name "unconnected-(U$1-PadD13)") (class "Default")
      (node (ref "U$1") (pin "D13") (pinfunction "D13_D13") (pintype "bidirectional"))
    )
    (net (code "91") (name "unconnected-(U$1-PadD14)") (class "Default")
      (node (ref "U$1") (pin "D14") (pinfunction "D14_D14") (pintype "bidirectional"))
    )
    (net (code "92") (name "unconnected-(U$1-PadD15)") (class "Default")
      (node (ref "U$1") (pin "D15") (pinfunction "D15_D15") (pintype "bidirectional"))
    )
    (net (code "93") (name "unconnected-(U$1-PadE)") (class "Default")
      (node (ref "U$1") (pin "E") (pinfunction "E_E") (pintype "bidirectional"))
    )
    (net (code "94") (name "unconnected-(U$1-PadR{slash}W)") (class "Default")
      (node (ref "U$1") (pin "R/W") (pinfunction "R/W_R/W") (pintype "bidirectional"))
    )
    (net (code "95") (name "unconnected-(U$1-Pad{slash}AS)") (class "Default")
      (node (ref "U$1") (pin "/AS") (pinfunction "/AS_/AS") (pintype "bidirectional"))
    )
    (net (code "96") (name "unconnected-(U$1-Pad{slash}BOOT)") (class "Default")
      (node (ref "U$1") (pin "/BOOT") (pinfunction "/BOOT_/BOOT") (pintype "bidirectional"))
    )
    (net (code "97") (name "unconnected-(U$1-Pad{slash}CLOCK)") (class "Default")
      (node (ref "U$1") (pin "/CLOCK") (pinfunction "/CLOCK_/CLOCK") (pintype "bidirectional"))
    )
    (net (code "98") (name "unconnected-(U$1-Pad{slash}LDS)") (class "Default")
      (node (ref "U$1") (pin "/LDS") (pinfunction "/LDS_/LDS") (pintype "bidirectional"))
    )
    (net (code "99") (name "unconnected-(U$1-Pad{slash}RESET)") (class "Default")
      (node (ref "U$1") (pin "/RESET") (pinfunction "/RESET_/RESET") (pintype "bidirectional"))
    )
    (net (code "100") (name "unconnected-(U$1-Pad{slash}UDS)") (class "Default")
      (node (ref "U$1") (pin "/UDS") (pinfunction "/UDS_/UDS") (pintype "bidirectional"))
    )
    (net (code "101") (name "unconnected-(U$1-Pad{slash}VMA)") (class "Default")
      (node (ref "U$1") (pin "/VMA") (pinfunction "/VMA_/VMA") (pintype "bidirectional"))
    )
    (net (code "102") (name "unconnected-(U$1-Pad{slash}VPA)") (class "Default")
      (node (ref "U$1") (pin "/VPA") (pinfunction "/VPA_/VPA") (pintype "bidirectional"))
    )
  )
)
